# o32h.net
KiCad netlist of a schematic drawn in EAGLE
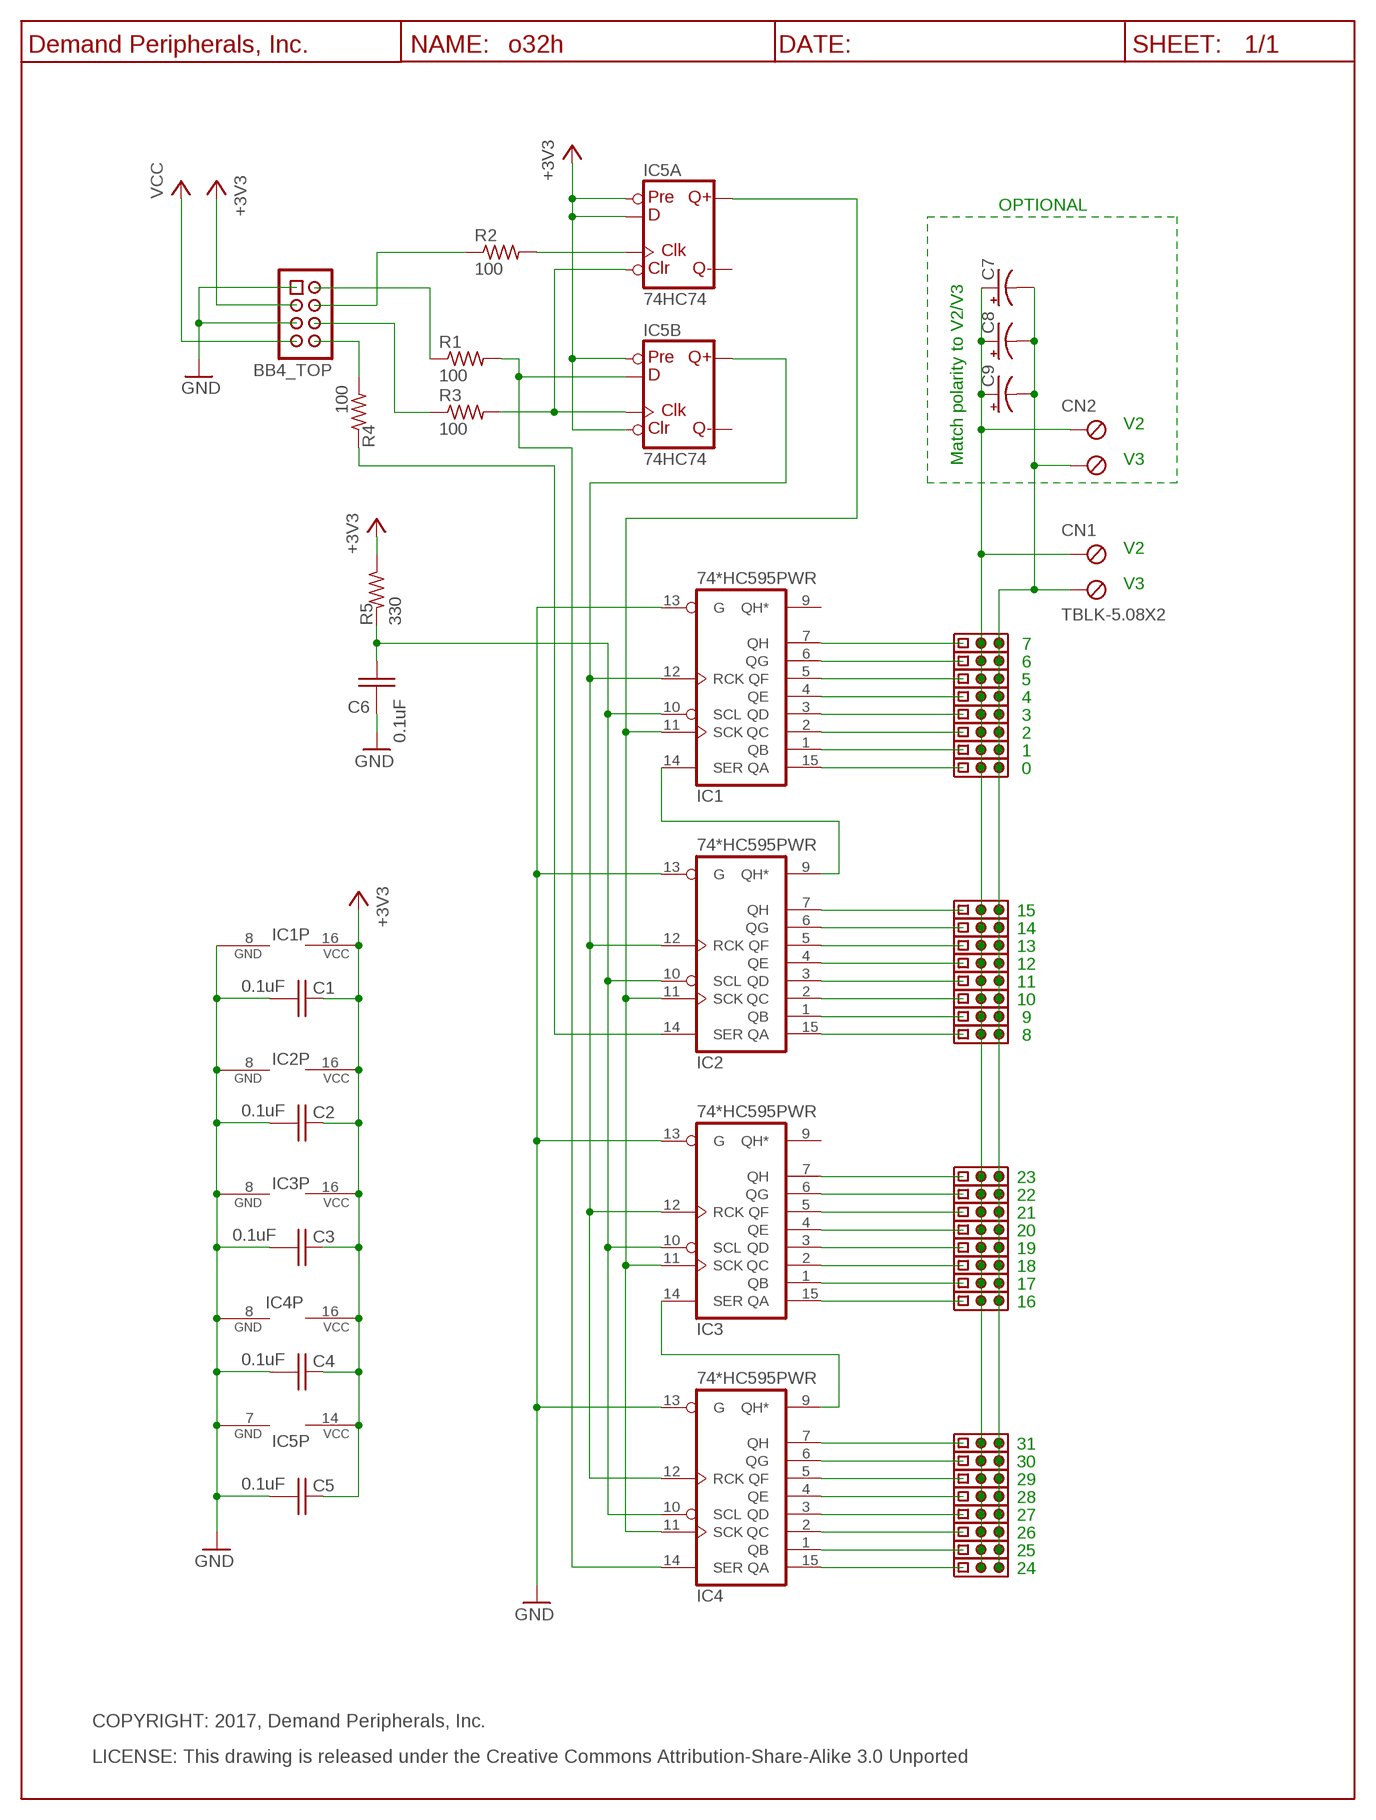
[diagram p0: schematic, sheet 1]

(export (version "E")
  (design (tool "Eeschema 10.0.6"))
  (components
    (comp (ref "BB4_TOP")
      (value "Keyed_Pin_Header_4x2(0.1\"x0.1\")")
      (footprint "eagle-import:HDR-4X2")
      (libsource (lib "eagle-import") (part "HDR-4X2-SHR"))
    )
    (comp (ref "C1")
      (value "0.1uF")
      (footprint "eagle-import:C0603")
      (libsource (lib "eagle-import") (part "C0.1UF_C0603"))
    )
    (comp (ref "C2")
      (value "0.1uF")
      (footprint "eagle-import:C0603")
      (libsource (lib "eagle-import") (part "C0.1UF_C0603"))
    )
    (comp (ref "C3")
      (value "0.1uF")
      (footprint "eagle-import:C0603")
      (libsource (lib "eagle-import") (part "C0.1UF_C0603"))
    )
    (comp (ref "C4")
      (value "0.1uF")
      (footprint "eagle-import:C0603")
      (libsource (lib "eagle-import") (part "C0.1UF_C0603"))
    )
    (comp (ref "C5")
      (value "0.1uF")
      (footprint "eagle-import:C0603")
      (libsource (lib "eagle-import") (part "C0.1UF_C0603"))
    )
    (comp (ref "C6")
      (value "0.1uF")
      (footprint "eagle-import:C0603")
      (libsource (lib "eagle-import") (part "C0.1UF_C0603"))
    )
    (comp (ref "C7")
      (value "OPTIONAL")
      (footprint "eagle-import:E7,5-16")
      (libsource (lib "eagle-import") (part "C1500UF35V_E7,5-16"))
    )
    (comp (ref "C8")
      (value "OPTIONAL")
      (footprint "eagle-import:E7,5-16")
      (libsource (lib "eagle-import") (part "C1500UF35V_E7,5-16"))
    )
    (comp (ref "C9")
      (value "OPTIONAL")
      (footprint "eagle-import:E7,5-16")
      (libsource (lib "eagle-import") (part "C1500UF35V_E7,5-16"))
    )
    (comp (ref "CN1")
      (value "TBLK-5.08X2")
      (footprint "eagle-import:TBLK-5.08-X2")
      (libsource (lib "eagle-import") (part "TBLK-5.08-X2"))
    )
    (comp (ref "CN2")
      (value "TBLK-5.08X2")
      (footprint "eagle-import:TBLK-5.08-X2")
      (libsource (lib "eagle-import") (part "TBLK-5.08-X2"))
    )
    (comp (ref "IC1")
      (value "74*HC595PWR")
      (footprint "eagle-import:SO16")
      (libsource (lib "eagle-import") (part "74595"))
    )
    (comp (ref "IC2")
      (value "74*HC595PWR")
      (footprint "eagle-import:SO16")
      (libsource (lib "eagle-import") (part "74595"))
    )
    (comp (ref "IC3")
      (value "74*HC595PWR")
      (footprint "eagle-import:SO16")
      (libsource (lib "eagle-import") (part "74595"))
    )
    (comp (ref "IC4")
      (value "74*HC595PWR")
      (footprint "eagle-import:SO16")
      (libsource (lib "eagle-import") (part "74595"))
    )
    (comp (ref "IC5")
      (value "74HC74")
      (footprint "eagle-import:SO14")
      (libsource (lib "eagle-import") (part "74AHC74SS"))
    )
    (comp (ref "R1")
      (value "100")
      (footprint "eagle-import:R0603")
      (libsource (lib "eagle-import") (part "R100_R0603"))
    )
    (comp (ref "R2")
      (value "100")
      (footprint "eagle-import:R0603")
      (libsource (lib "eagle-import") (part "R100_R0603"))
    )
    (comp (ref "R3")
      (value "100")
      (footprint "eagle-import:R0603")
      (libsource (lib "eagle-import") (part "R100_R0603"))
    )
    (comp (ref "R4")
      (value "100")
      (footprint "eagle-import:R0603")
      (libsource (lib "eagle-import") (part "R100_R0603"))
    )
    (comp (ref "R5")
      (value "330")
      (footprint "eagle-import:R0603")
      (libsource (lib "eagle-import") (part "R330_R0603"))
    )
    (comp (ref "U$2")
      (value "DP_FRAME_P")
      (footprint "eagle-import:P_FRAME")
      (libsource (lib "eagle-import") (part "DP_FRAME_P"))
    )
    (comp (ref "U$8")
      (value "HDR-3X1")
      (footprint "eagle-import:HDR-3X1")
      (libsource (lib "eagle-import") (part "HDR-3X1"))
    )
    (comp (ref "U$9")
      (value "HDR-3X1")
      (footprint "eagle-import:HDR-3X1")
      (libsource (lib "eagle-import") (part "HDR-3X1"))
    )
    (comp (ref "U$10")
      (value "HDR-3X1")
      (footprint "eagle-import:HDR-3X1")
      (libsource (lib "eagle-import") (part "HDR-3X1"))
    )
    (comp (ref "U$11")
      (value "HDR-3X1")
      (footprint "eagle-import:HDR-3X1")
      (libsource (lib "eagle-import") (part "HDR-3X1"))
    )
    (comp (ref "U$12")
      (value "HDR-3X1")
      (footprint "eagle-import:HDR-3X1")
      (libsource (lib "eagle-import") (part "HDR-3X1"))
    )
    (comp (ref "U$13")
      (value "HDR-3X1")
      (footprint "eagle-import:HDR-3X1")
      (libsource (lib "eagle-import") (part "HDR-3X1"))
    )
    (comp (ref "U$14")
      (value "HDR-3X1")
      (footprint "eagle-import:HDR-3X1")
      (libsource (lib "eagle-import") (part "HDR-3X1"))
    )
    (comp (ref "U$15")
      (value "HDR-3X1")
      (footprint "eagle-import:HDR-3X1")
      (libsource (lib "eagle-import") (part "HDR-3X1"))
    )
    (comp (ref "U$16")
      (value "HDR-3X1")
      (footprint "eagle-import:HDR-3X1")
      (libsource (lib "eagle-import") (part "HDR-3X1"))
    )
    (comp (ref "U$17")
      (value "HDR-3X1")
      (footprint "eagle-import:HDR-3X1")
      (libsource (lib "eagle-import") (part "HDR-3X1"))
    )
    (comp (ref "U$18")
      (value "HDR-3X1")
      (footprint "eagle-import:HDR-3X1")
      (libsource (lib "eagle-import") (part "HDR-3X1"))
    )
    (comp (ref "U$19")
      (value "HDR-3X1")
      (footprint "eagle-import:HDR-3X1")
      (libsource (lib "eagle-import") (part "HDR-3X1"))
    )
    (comp (ref "U$20")
      (value "HDR-3X1")
      (footprint "eagle-import:HDR-3X1")
      (libsource (lib "eagle-import") (part "HDR-3X1"))
    )
    (comp (ref "U$21")
      (value "HDR-3X1")
      (footprint "eagle-import:HDR-3X1")
      (libsource (lib "eagle-import") (part "HDR-3X1"))
    )
    (comp (ref "U$22")
      (value "HDR-3X1")
      (footprint "eagle-import:HDR-3X1")
      (libsource (lib "eagle-import") (part "HDR-3X1"))
    )
    (comp (ref "U$23")
      (value "HDR-3X1")
      (footprint "eagle-import:HDR-3X1")
      (libsource (lib "eagle-import") (part "HDR-3X1"))
    )
    (comp (ref "U$24")
      (value "HDR-3X1")
      (footprint "eagle-import:HDR-3X1")
      (libsource (lib "eagle-import") (part "HDR-3X1"))
    )
    (comp (ref "U$25")
      (value "HDR-3X1")
      (footprint "eagle-import:HDR-3X1")
      (libsource (lib "eagle-import") (part "HDR-3X1"))
    )
    (comp (ref "U$26")
      (value "HDR-3X1")
      (footprint "eagle-import:HDR-3X1")
      (libsource (lib "eagle-import") (part "HDR-3X1"))
    )
    (comp (ref "U$27")
      (value "HDR-3X1")
      (footprint "eagle-import:HDR-3X1")
      (libsource (lib "eagle-import") (part "HDR-3X1"))
    )
    (comp (ref "U$28")
      (value "HDR-3X1")
      (footprint "eagle-import:HDR-3X1")
      (libsource (lib "eagle-import") (part "HDR-3X1"))
    )
    (comp (ref "U$29")
      (value "HDR-3X1")
      (footprint "eagle-import:HDR-3X1")
      (libsource (lib "eagle-import") (part "HDR-3X1"))
    )
    (comp (ref "U$30")
      (value "HDR-3X1")
      (footprint "eagle-import:HDR-3X1")
      (libsource (lib "eagle-import") (part "HDR-3X1"))
    )
    (comp (ref "U$31")
      (value "HDR-3X1")
      (footprint "eagle-import:HDR-3X1")
      (libsource (lib "eagle-import") (part "HDR-3X1"))
    )
    (comp (ref "U$32")
      (value "HDR-3X1")
      (footprint "eagle-import:HDR-3X1")
      (libsource (lib "eagle-import") (part "HDR-3X1"))
    )
    (comp (ref "U$33")
      (value "HDR-3X1")
      (footprint "eagle-import:HDR-3X1")
      (libsource (lib "eagle-import") (part "HDR-3X1"))
    )
    (comp (ref "U$34")
      (value "HDR-3X1")
      (footprint "eagle-import:HDR-3X1")
      (libsource (lib "eagle-import") (part "HDR-3X1"))
    )
    (comp (ref "U$35")
      (value "HDR-3X1")
      (footprint "eagle-import:HDR-3X1")
      (libsource (lib "eagle-import") (part "HDR-3X1"))
    )
    (comp (ref "U$36")
      (value "HDR-3X1")
      (footprint "eagle-import:HDR-3X1")
      (libsource (lib "eagle-import") (part "HDR-3X1"))
    )
    (comp (ref "U$37")
      (value "HDR-3X1")
      (footprint "eagle-import:HDR-3X1")
      (libsource (lib "eagle-import") (part "HDR-3X1"))
    )
    (comp (ref "U$38")
      (value "HDR-3X1")
      (footprint "eagle-import:HDR-3X1")
      (libsource (lib "eagle-import") (part "HDR-3X1"))
    )
    (comp (ref "U$39")
      (value "HDR-3X1")
      (footprint "eagle-import:HDR-3X1")
      (libsource (lib "eagle-import") (part "HDR-3X1"))
    )
  )
  (nets
    (net (code "1") (name "+3V3") (class "Default")
      (node (ref "BB4_TOP") (pin "3") (pinfunction "3_3") (pintype "passive"))
      (node (ref "C1") (pin "1") (pinfunction "1_1") (pintype "passive"))
      (node (ref "C2") (pin "1") (pinfunction "1_1") (pintype "passive"))
      (node (ref "C3") (pin "1") (pinfunction "1_1") (pintype "passive"))
      (node (ref "C4") (pin "1") (pinfunction "1_1") (pintype "passive"))
      (node (ref "C5") (pin "1") (pinfunction "1_1") (pintype "passive"))
      (node (ref "IC1") (pin "16") (pinfunction "VCC_16") (pintype "power_in"))
      (node (ref "IC2") (pin "16") (pinfunction "VCC_16") (pintype "power_in"))
      (node (ref "IC3") (pin "16") (pinfunction "VCC_16") (pintype "power_in"))
      (node (ref "IC4") (pin "16") (pinfunction "VCC_16") (pintype "power_in"))
      (node (ref "IC5") (pin "10") (pinfunction "PRE_10") (pintype "input"))
      (node (ref "IC5") (pin "13") (pinfunction "CLR_13") (pintype "input"))
      (node (ref "IC5") (pin "14") (pinfunction "VCC_14") (pintype "power_in"))
      (node (ref "IC5") (pin "2") (pinfunction "D_2") (pintype "input"))
      (node (ref "IC5") (pin "4") (pinfunction "PRE_4") (pintype "input"))
      (node (ref "R5") (pin "1") (pinfunction "1_1") (pintype "passive"))
    )
    (net (code "2") (name "GND") (class "Default")
      (node (ref "BB4_TOP") (pin "1") (pinfunction "1_1") (pintype "passive"))
      (node (ref "BB4_TOP") (pin "5") (pinfunction "5_5") (pintype "passive"))
      (node (ref "C1") (pin "2") (pinfunction "2_2") (pintype "passive"))
      (node (ref "C2") (pin "2") (pinfunction "2_2") (pintype "passive"))
      (node (ref "C3") (pin "2") (pinfunction "2_2") (pintype "passive"))
      (node (ref "C4") (pin "2") (pinfunction "2_2") (pintype "passive"))
      (node (ref "C5") (pin "2") (pinfunction "2_2") (pintype "passive"))
      (node (ref "C6") (pin "2") (pinfunction "2_2") (pintype "passive"))
      (node (ref "IC1") (pin "13") (pinfunction "G_13") (pintype "input"))
      (node (ref "IC1") (pin "8") (pinfunction "GND_8") (pintype "power_in"))
      (node (ref "IC2") (pin "13") (pinfunction "G_13") (pintype "input"))
      (node (ref "IC2") (pin "8") (pinfunction "GND_8") (pintype "power_in"))
      (node (ref "IC3") (pin "13") (pinfunction "G_13") (pintype "input"))
      (node (ref "IC3") (pin "8") (pinfunction "GND_8") (pintype "power_in"))
      (node (ref "IC4") (pin "13") (pinfunction "G_13") (pintype "input"))
      (node (ref "IC4") (pin "8") (pinfunction "GND_8") (pintype "power_in"))
      (node (ref "IC5") (pin "7") (pinfunction "GND_7") (pintype "power_in"))
    )
    (net (code "3") (name "Net-(BB4_TOP-Pad2)") (class "Default")
      (node (ref "BB4_TOP") (pin "2") (pinfunction "2_2") (pintype "passive"))
      (node (ref "R1") (pin "1") (pinfunction "1_1") (pintype "passive"))
    )
    (net (code "4") (name "Net-(BB4_TOP-Pad4)") (class "Default")
      (node (ref "BB4_TOP") (pin "4") (pinfunction "4_4") (pintype "passive"))
      (node (ref "R2") (pin "1") (pinfunction "1_1") (pintype "passive"))
    )
    (net (code "5") (name "Net-(BB4_TOP-Pad6)") (class "Default")
      (node (ref "BB4_TOP") (pin "6") (pinfunction "6_6") (pintype "passive"))
      (node (ref "R3") (pin "1") (pinfunction "1_1") (pintype "passive"))
    )
    (net (code "6") (name "Net-(BB4_TOP-Pad8)") (class "Default")
      (node (ref "BB4_TOP") (pin "8") (pinfunction "8_8") (pintype "passive"))
      (node (ref "R4") (pin "2") (pinfunction "2_2") (pintype "passive"))
    )
    (net (code "7") (name "Net-(CN1-KL)") (class "Default")
      (node (ref "C7") (pin "+") (pinfunction "+_+") (pintype "passive"))
      (node (ref "C8") (pin "+") (pinfunction "+_+") (pintype "passive"))
      (node (ref "C9") (pin "+") (pinfunction "+_+") (pintype "passive"))
      (node (ref "CN1") (pin "1") (pinfunction "KL_1") (pintype "passive"))
      (node (ref "CN2") (pin "1") (pinfunction "KL_1") (pintype "passive"))
      (node (ref "U$10") (pin "2") (pinfunction "2_2") (pintype "passive"))
      (node (ref "U$11") (pin "2") (pinfunction "2_2") (pintype "passive"))
      (node (ref "U$12") (pin "2") (pinfunction "2_2") (pintype "passive"))
      (node (ref "U$13") (pin "2") (pinfunction "2_2") (pintype "passive"))
      (node (ref "U$14") (pin "2") (pinfunction "2_2") (pintype "passive"))
      (node (ref "U$15") (pin "2") (pinfunction "2_2") (pintype "passive"))
      (node (ref "U$16") (pin "2") (pinfunction "2_2") (pintype "passive"))
      (node (ref "U$17") (pin "2") (pinfunction "2_2") (pintype "passive"))
      (node (ref "U$18") (pin "2") (pinfunction "2_2") (pintype "passive"))
      (node (ref "U$19") (pin "2") (pinfunction "2_2") (pintype "passive"))
      (node (ref "U$20") (pin "2") (pinfunction "2_2") (pintype "passive"))
      (node (ref "U$21") (pin "2") (pinfunction "2_2") (pintype "passive"))
      (node (ref "U$22") (pin "2") (pinfunction "2_2") (pintype "passive"))
      (node (ref "U$23") (pin "2") (pinfunction "2_2") (pintype "passive"))
      (node (ref "U$24") (pin "2") (pinfunction "2_2") (pintype "passive"))
      (node (ref "U$25") (pin "2") (pinfunction "2_2") (pintype "passive"))
      (node (ref "U$26") (pin "2") (pinfunction "2_2") (pintype "passive"))
      (node (ref "U$27") (pin "2") (pinfunction "2_2") (pintype "passive"))
      (node (ref "U$28") (pin "2") (pinfunction "2_2") (pintype "passive"))
      (node (ref "U$29") (pin "2") (pinfunction "2_2") (pintype "passive"))
      (node (ref "U$30") (pin "2") (pinfunction "2_2") (pintype "passive"))
      (node (ref "U$31") (pin "2") (pinfunction "2_2") (pintype "passive"))
      (node (ref "U$32") (pin "2") (pinfunction "2_2") (pintype "passive"))
      (node (ref "U$33") (pin "2") (pinfunction "2_2") (pintype "passive"))
      (node (ref "U$34") (pin "2") (pinfunction "2_2") (pintype "passive"))
      (node (ref "U$35") (pin "2") (pinfunction "2_2") (pintype "passive"))
      (node (ref "U$36") (pin "2") (pinfunction "2_2") (pintype "passive"))
      (node (ref "U$37") (pin "2") (pinfunction "2_2") (pintype "passive"))
      (node (ref "U$38") (pin "2") (pinfunction "2_2") (pintype "passive"))
      (node (ref "U$39") (pin "2") (pinfunction "2_2") (pintype "passive"))
      (node (ref "U$8") (pin "2") (pinfunction "2_2") (pintype "passive"))
      (node (ref "U$9") (pin "2") (pinfunction "2_2") (pintype "passive"))
    )
    (net (code "8") (name "Net-(CN1-KL1)") (class "Default")
      (node (ref "C7") (pin "-") (pinfunction "-_-") (pintype "passive"))
      (node (ref "C8") (pin "-") (pinfunction "-_-") (pintype "passive"))
      (node (ref "C9") (pin "-") (pinfunction "-_-") (pintype "passive"))
      (node (ref "CN1") (pin "2") (pinfunction "KL1_2") (pintype "passive"))
      (node (ref "CN2") (pin "2") (pinfunction "KL1_2") (pintype "passive"))
      (node (ref "U$10") (pin "3") (pinfunction "3_3") (pintype "passive"))
      (node (ref "U$11") (pin "3") (pinfunction "3_3") (pintype "passive"))
      (node (ref "U$12") (pin "3") (pinfunction "3_3") (pintype "passive"))
      (node (ref "U$13") (pin "3") (pinfunction "3_3") (pintype "passive"))
      (node (ref "U$14") (pin "3") (pinfunction "3_3") (pintype "passive"))
      (node (ref "U$15") (pin "3") (pinfunction "3_3") (pintype "passive"))
      (node (ref "U$16") (pin "3") (pinfunction "3_3") (pintype "passive"))
      (node (ref "U$17") (pin "3") (pinfunction "3_3") (pintype "passive"))
      (node (ref "U$18") (pin "3") (pinfunction "3_3") (pintype "passive"))
      (node (ref "U$19") (pin "3") (pinfunction "3_3") (pintype "passive"))
      (node (ref "U$20") (pin "3") (pinfunction "3_3") (pintype "passive"))
      (node (ref "U$21") (pin "3") (pinfunction "3_3") (pintype "passive"))
      (node (ref "U$22") (pin "3") (pinfunction "3_3") (pintype "passive"))
      (node (ref "U$23") (pin "3") (pinfunction "3_3") (pintype "passive"))
      (node (ref "U$24") (pin "3") (pinfunction "3_3") (pintype "passive"))
      (node (ref "U$25") (pin "3") (pinfunction "3_3") (pintype "passive"))
      (node (ref "U$26") (pin "3") (pinfunction "3_3") (pintype "passive"))
      (node (ref "U$27") (pin "3") (pinfunction "3_3") (pintype "passive"))
      (node (ref "U$28") (pin "3") (pinfunction "3_3") (pintype "passive"))
      (node (ref "U$29") (pin "3") (pinfunction "3_3") (pintype "passive"))
      (node (ref "U$30") (pin "3") (pinfunction "3_3") (pintype "passive"))
      (node (ref "U$31") (pin "3") (pinfunction "3_3") (pintype "passive"))
      (node (ref "U$32") (pin "3") (pinfunction "3_3") (pintype "passive"))
      (node (ref "U$33") (pin "3") (pinfunction "3_3") (pintype "passive"))
      (node (ref "U$34") (pin "3") (pinfunction "3_3") (pintype "passive"))
      (node (ref "U$35") (pin "3") (pinfunction "3_3") (pintype "passive"))
      (node (ref "U$36") (pin "3") (pinfunction "3_3") (pintype "passive"))
      (node (ref "U$37") (pin "3") (pinfunction "3_3") (pintype "passive"))
      (node (ref "U$38") (pin "3") (pinfunction "3_3") (pintype "passive"))
      (node (ref "U$39") (pin "3") (pinfunction "3_3") (pintype "passive"))
      (node (ref "U$8") (pin "3") (pinfunction "3_3") (pintype "passive"))
      (node (ref "U$9") (pin "3") (pinfunction "3_3") (pintype "passive"))
    )
    (net (code "9") (name "Net-(IC1A-QA)") (class "Default")
      (node (ref "IC1") (pin "15") (pinfunction "QA_15") (pintype "tri_state"))
      (node (ref "U$15") (pin "1") (pinfunction "1_1") (pintype "passive"))
    )
    (net (code "10") (name "Net-(IC1A-QB)") (class "Default")
      (node (ref "IC1") (pin "1") (pinfunction "QB_1") (pintype "tri_state"))
      (node (ref "U$14") (pin "1") (pinfunction "1_1") (pintype "passive"))
    )
    (net (code "11") (name "Net-(IC1A-QC)") (class "Default")
      (node (ref "IC1") (pin "2") (pinfunction "QC_2") (pintype "tri_state"))
      (node (ref "U$13") (pin "1") (pinfunction "1_1") (pintype "passive"))
    )
    (net (code "12") (name "Net-(IC1A-QD)") (class "Default")
      (node (ref "IC1") (pin "3") (pinfunction "QD_3") (pintype "tri_state"))
      (node (ref "U$12") (pin "1") (pinfunction "1_1") (pintype "passive"))
    )
    (net (code "13") (name "Net-(IC1A-QE)") (class "Default")
      (node (ref "IC1") (pin "4") (pinfunction "QE_4") (pintype "tri_state"))
      (node (ref "U$11") (pin "1") (pinfunction "1_1") (pintype "passive"))
    )
    (net (code "14") (name "Net-(IC1A-QF)") (class "Default")
      (node (ref "IC1") (pin "5") (pinfunction "QF_5") (pintype "tri_state"))
      (node (ref "U$10") (pin "1") (pinfunction "1_1") (pintype "passive"))
    )
    (net (code "15") (name "Net-(IC1A-QG)") (class "Default")
      (node (ref "IC1") (pin "6") (pinfunction "QG_6") (pintype "tri_state"))
      (node (ref "U$9") (pin "1") (pinfunction "1_1") (pintype "passive"))
    )
    (net (code "16") (name "Net-(IC1A-QH)") (class "Default")
      (node (ref "IC1") (pin "7") (pinfunction "QH_7") (pintype "tri_state"))
      (node (ref "U$8") (pin "1") (pinfunction "1_1") (pintype "passive"))
    )
    (net (code "17") (name "Net-(IC1A-RCK)") (class "Default")
      (node (ref "IC1") (pin "12") (pinfunction "RCK_12") (pintype "input"))
      (node (ref "IC2") (pin "12") (pinfunction "RCK_12") (pintype "input"))
      (node (ref "IC3") (pin "12") (pinfunction "RCK_12") (pintype "input"))
      (node (ref "IC4") (pin "12") (pinfunction "RCK_12") (pintype "input"))
      (node (ref "IC5") (pin "9") (pinfunction "Q_9") (pintype "output"))
    )
    (net (code "18") (name "Net-(IC1A-SCK)") (class "Default")
      (node (ref "IC1") (pin "11") (pinfunction "SCK_11") (pintype "input"))
      (node (ref "IC2") (pin "11") (pinfunction "SCK_11") (pintype "input"))
      (node (ref "IC3") (pin "11") (pinfunction "SCK_11") (pintype "input"))
      (node (ref "IC4") (pin "11") (pinfunction "SCK_11") (pintype "input"))
      (node (ref "IC5") (pin "5") (pinfunction "Q_5") (pintype "output"))
    )
    (net (code "19") (name "Net-(IC1A-SCL)") (class "Default")
      (node (ref "C6") (pin "1") (pinfunction "1_1") (pintype "passive"))
      (node (ref "IC1") (pin "10") (pinfunction "SCL_10") (pintype "input"))
      (node (ref "IC2") (pin "10") (pinfunction "SCL_10") (pintype "input"))
      (node (ref "IC3") (pin "10") (pinfunction "SCL_10") (pintype "input"))
      (node (ref "IC4") (pin "10") (pinfunction "SCL_10") (pintype "input"))
      (node (ref "R5") (pin "2") (pinfunction "2_2") (pintype "passive"))
    )
    (net (code "20") (name "Net-(IC1A-SER)") (class "Default")
      (node (ref "IC1") (pin "14") (pinfunction "SER_14") (pintype "input"))
      (node (ref "IC2") (pin "9") (pinfunction "QH*_9") (pintype "tri_state"))
    )
    (net (code "21") (name "Net-(IC2A-QA)") (class "Default")
      (node (ref "IC2") (pin "15") (pinfunction "QA_15") (pintype "tri_state"))
      (node (ref "U$23") (pin "1") (pinfunction "1_1") (pintype "passive"))
    )
    (net (code "22") (name "Net-(IC2A-QB)") (class "Default")
      (node (ref "IC2") (pin "1") (pinfunction "QB_1") (pintype "tri_state"))
      (node (ref "U$22") (pin "1") (pinfunction "1_1") (pintype "passive"))
    )
    (net (code "23") (name "Net-(IC2A-QC)") (class "Default")
      (node (ref "IC2") (pin "2") (pinfunction "QC_2") (pintype "tri_state"))
      (node (ref "U$21") (pin "1") (pinfunction "1_1") (pintype "passive"))
    )
    (net (code "24") (name "Net-(IC2A-QD)") (class "Default")
      (node (ref "IC2") (pin "3") (pinfunction "QD_3") (pintype "tri_state"))
      (node (ref "U$20") (pin "1") (pinfunction "1_1") (pintype "passive"))
    )
    (net (code "25") (name "Net-(IC2A-QE)") (class "Default")
      (node (ref "IC2") (pin "4") (pinfunction "QE_4") (pintype "tri_state"))
      (node (ref "U$19") (pin "1") (pinfunction "1_1") (pintype "passive"))
    )
    (net (code "26") (name "Net-(IC2A-QF)") (class "Default")
      (node (ref "IC2") (pin "5") (pinfunction "QF_5") (pintype "tri_state"))
      (node (ref "U$18") (pin "1") (pinfunction "1_1") (pintype "passive"))
    )
    (net (code "27") (name "Net-(IC2A-QG)") (class "Default")
      (node (ref "IC2") (pin "6") (pinfunction "QG_6") (pintype "tri_state"))
      (node (ref "U$17") (pin "1") (pinfunction "1_1") (pintype "passive"))
    )
    (net (code "28") (name "Net-(IC2A-QH)") (class "Default")
      (node (ref "IC2") (pin "7") (pinfunction "QH_7") (pintype "tri_state"))
      (node (ref "U$16") (pin "1") (pinfunction "1_1") (pintype "passive"))
    )
    (net (code "29") (name "Net-(IC2A-SER)") (class "Default")
      (node (ref "IC2") (pin "14") (pinfunction "SER_14") (pintype "input"))
      (node (ref "R4") (pin "1") (pinfunction "1_1") (pintype "passive"))
    )
    (net (code "30") (name "Net-(IC3A-QA)") (class "Default")
      (node (ref "IC3") (pin "15") (pinfunction "QA_15") (pintype "tri_state"))
      (node (ref "U$31") (pin "1") (pinfunction "1_1") (pintype "passive"))
    )
    (net (code "31") (name "Net-(IC3A-QB)") (class "Default")
      (node (ref "IC3") (pin "1") (pinfunction "QB_1") (pintype "tri_state"))
      (node (ref "U$30") (pin "1") (pinfunction "1_1") (pintype "passive"))
    )
    (net (code "32") (name "Net-(IC3A-QC)") (class "Default")
      (node (ref "IC3") (pin "2") (pinfunction "QC_2") (pintype "tri_state"))
      (node (ref "U$29") (pin "1") (pinfunction "1_1") (pintype "passive"))
    )
    (net (code "33") (name "Net-(IC3A-QD)") (class "Default")
      (node (ref "IC3") (pin "3") (pinfunction "QD_3") (pintype "tri_state"))
      (node (ref "U$28") (pin "1") (pinfunction "1_1") (pintype "passive"))
    )
    (net (code "34") (name "Net-(IC3A-QE)") (class "Default")
      (node (ref "IC3") (pin "4") (pinfunction "QE_4") (pintype "tri_state"))
      (node (ref "U$27") (pin "1") (pinfunction "1_1") (pintype "passive"))
    )
    (net (code "35") (name "Net-(IC3A-QF)") (class "Default")
      (node (ref "IC3") (pin "5") (pinfunction "QF_5") (pintype "tri_state"))
      (node (ref "U$26") (pin "1") (pinfunction "1_1") (pintype "passive"))
    )
    (net (code "36") (name "Net-(IC3A-QG)") (class "Default")
      (node (ref "IC3") (pin "6") (pinfunction "QG_6") (pintype "tri_state"))
      (node (ref "U$25") (pin "1") (pinfunction "1_1") (pintype "passive"))
    )
    (net (code "37") (name "Net-(IC3A-QH)") (class "Default")
      (node (ref "IC3") (pin "7") (pinfunction "QH_7") (pintype "tri_state"))
      (node (ref "U$24") (pin "1") (pinfunction "1_1") (pintype "passive"))
    )
    (net (code "38") (name "Net-(IC3A-SER)") (class "Default")
      (node (ref "IC3") (pin "14") (pinfunction "SER_14") (pintype "input"))
      (node (ref "IC4") (pin "9") (pinfunction "QH*_9") (pintype "tri_state"))
    )
    (net (code "39") (name "Net-(IC4A-QA)") (class "Default")
      (node (ref "IC4") (pin "15") (pinfunction "QA_15") (pintype "tri_state"))
      (node (ref "U$39") (pin "1") (pinfunction "1_1") (pintype "passive"))
    )
    (net (code "40") (name "Net-(IC4A-QB)") (class "Default")
      (node (ref "IC4") (pin "1") (pinfunction "QB_1") (pintype "tri_state"))
      (node (ref "U$38") (pin "1") (pinfunction "1_1") (pintype "passive"))
    )
    (net (code "41") (name "Net-(IC4A-QC)") (class "Default")
      (node (ref "IC4") (pin "2") (pinfunction "QC_2") (pintype "tri_state"))
      (node (ref "U$37") (pin "1") (pinfunction "1_1") (pintype "passive"))
    )
    (net (code "42") (name "Net-(IC4A-QD)") (class "Default")
      (node (ref "IC4") (pin "3") (pinfunction "QD_3") (pintype "tri_state"))
      (node (ref "U$36") (pin "1") (pinfunction "1_1") (pintype "passive"))
    )
    (net (code "43") (name "Net-(IC4A-QE)") (class "Default")
      (node (ref "IC4") (pin "4") (pinfunction "QE_4") (pintype "tri_state"))
      (node (ref "U$35") (pin "1") (pinfunction "1_1") (pintype "passive"))
    )
    (net (code "44") (name "Net-(IC4A-QF)") (class "Default")
      (node (ref "IC4") (pin "5") (pinfunction "QF_5") (pintype "tri_state"))
      (node (ref "U$34") (pin "1") (pinfunction "1_1") (pintype "passive"))
    )
    (net (code "45") (name "Net-(IC4A-QG)") (class "Default")
      (node (ref "IC4") (pin "6") (pinfunction "QG_6") (pintype "tri_state"))
      (node (ref "U$33") (pin "1") (pinfunction "1_1") (pintype "passive"))
    )
    (net (code "46") (name "Net-(IC4A-QH)") (class "Default")
      (node (ref "IC4") (pin "7") (pinfunction "QH_7") (pintype "tri_state"))
      (node (ref "U$32") (pin "1") (pinfunction "1_1") (pintype "passive"))
    )
    (net (code "47") (name "Net-(IC4A-SER)") (class "Default")
      (node (ref "IC4") (pin "14") (pinfunction "SER_14") (pintype "input"))
      (node (ref "IC5") (pin "12") (pinfunction "D_12") (pintype "input"))
      (node (ref "R1") (pin "2") (pinfunction "2_2") (pintype "passive"))
    )
    (net (code "48") (name "Net-(IC5A-CLK)") (class "Default")
      (node (ref "IC5") (pin "3") (pinfunction "CLK_3") (pintype "input"))
      (node (ref "R2") (pin "2") (pinfunction "2_2") (pintype "passive"))
    )
    (net (code "49") (name "Net-(IC5A-CLR)") (class "Default")
      (node (ref "IC5") (pin "1") (pinfunction "CLR_1") (pintype "input"))
      (node (ref "IC5") (pin "11") (pinfunction "CLK_11") (pintype "input"))
      (node (ref "R3") (pin "2") (pinfunction "2_2") (pintype "passive"))
    )
    (net (code "50") (name "VCC") (class "Default")
      (node (ref "BB4_TOP") (pin "7") (pinfunction "7_7") (pintype "passive"))
    )
    (net (code "51") (name "unconnected-(IC1A-QH*-Pad9)") (class "Default")
      (node (ref "IC1") (pin "9") (pinfunction "QH*_9") (pintype "tri_state"))
    )
    (net (code "52") (name "unconnected-(IC3A-QH*-Pad9)") (class "Default")
      (node (ref "IC3") (pin "9") (pinfunction "QH*_9") (pintype "tri_state"))
    )
    (net (code "53") (name "unconnected-(IC5A-~{Q}-Pad6)") (class "Default")
      (node (ref "IC5") (pin "6") (pinfunction "~{Q}_6") (pintype "output"))
    )
    (net (code "54") (name "unconnected-(IC5B-~{Q}-Pad8)") (class "Default")
      (node (ref "IC5") (pin "8") (pinfunction "~{Q}_8") (pintype "output"))
    )
  )
)
